# piezo-preamp-tickler_V0-8.net
KiCad netlist of a schematic drawn in EAGLE
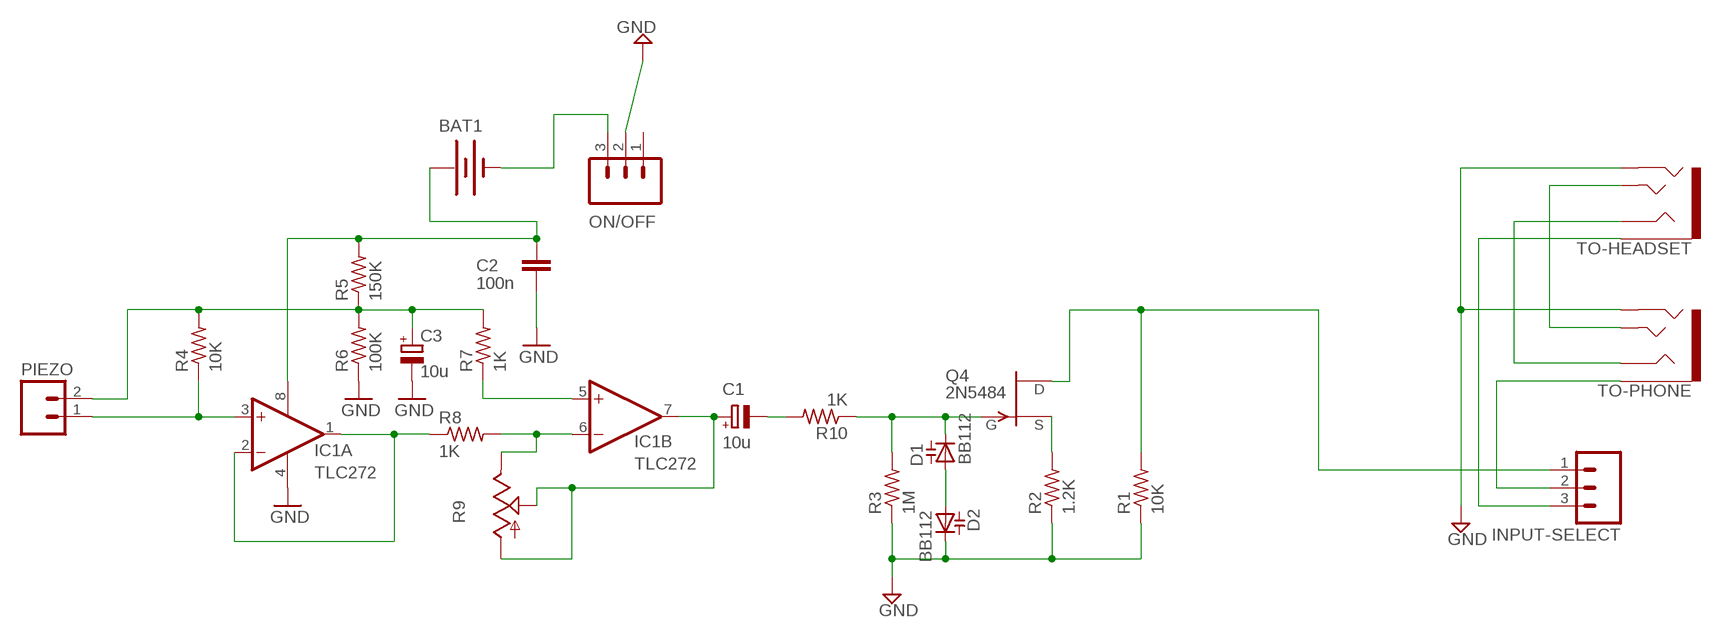
[diagram p0: schematic, sheet 1]

(export (version "E")
  (design (tool "Eeschema 10.0.6"))
  (components
    (comp (ref "BAT1")
      (value "BATTERYA23")
      (footprint "eagle-import:BATTERY-A23")
      (libsource (lib "eagle-import") (part "BATTERYA23"))
    )
    (comp (ref "C1")
      (value "10u")
      (footprint "eagle-import:E2,5-5")
      (libsource (lib "eagle-import") (part "CPOL-EUE2.5-5"))
    )
    (comp (ref "C2")
      (value "100n")
      (footprint "eagle-import:C025-025X050")
      (libsource (lib "eagle-import") (part "C-EU025-025X050"))
    )
    (comp (ref "C3")
      (value "10u")
      (footprint "eagle-import:E2,5-5")
      (libsource (lib "eagle-import") (part "CPOL-EUE2.5-5"))
    )
    (comp (ref "D1")
      (value "BB112")
      (footprint "eagle-import:SOT54H")
      (libsource (lib "eagle-import") (part "BB112"))
    )
    (comp (ref "D2")
      (value "BB112")
      (footprint "eagle-import:SOT54H")
      (libsource (lib "eagle-import") (part "BB112"))
    )
    (comp (ref "IC1")
      (value "TLC272")
      (footprint "eagle-import:DIL08")
      (libsource (lib "eagle-import") (part "TLC272P"))
    )
    (comp (ref "INPUT-SELECT")
      (value "M03SINGLE-POLE-DOUBLE-THROW")
      (footprint "eagle-import:SPDT-SWITCH")
      (libsource (lib "eagle-import") (part "M03SINGLE-POLE-DOUBLE-THROW"))
    )
    (comp (ref "ON/OFF")
      (value "labl")
      (footprint "eagle-import:SPDT-SWITCH")
      (libsource (lib "eagle-import") (part "M03SINGLE-POLE-DOUBLE-THROW"))
    )
    (comp (ref "PIEZO")
      (value "M02LOCK")
      (footprint "eagle-import:1X02_LOCK")
      (libsource (lib "eagle-import") (part "M02LOCK"))
    )
    (comp (ref "Q4")
      (value "2N5484")
      (footprint "eagle-import:TO92-")
      (libsource (lib "eagle-import") (part "?5482N4"))
    )
    (comp (ref "R1")
      (value "10K")
      (footprint "eagle-import:0204V")
      (libsource (lib "eagle-import") (part "R-US_0204/2V"))
    )
    (comp (ref "R2")
      (value "1.2K")
      (footprint "eagle-import:0204V")
      (libsource (lib "eagle-import") (part "R-US_0204/2V"))
    )
    (comp (ref "R3")
      (value "1M")
      (footprint "eagle-import:0204V")
      (libsource (lib "eagle-import") (part "R-US_0204/2V"))
    )
    (comp (ref "R4")
      (value "10K")
      (footprint "eagle-import:0204V")
      (libsource (lib "eagle-import") (part "R-US_0204/2V"))
    )
    (comp (ref "R5")
      (value "150K")
      (footprint "eagle-import:0204V")
      (libsource (lib "eagle-import") (part "R-US_0204/2V"))
    )
    (comp (ref "R6")
      (value "100K")
      (footprint "eagle-import:0204V")
      (libsource (lib "eagle-import") (part "R-US_0204/2V"))
    )
    (comp (ref "R7")
      (value "1K")
      (footprint "eagle-import:0204V")
      (libsource (lib "eagle-import") (part "R-US_0204/2V"))
    )
    (comp (ref "R8")
      (value "1K")
      (footprint "eagle-import:0204V")
      (libsource (lib "eagle-import") (part "R-US_0204/2V"))
    )
    (comp (ref "R9")
      (value "TRIM3386")
      (footprint "eagle-import:TRIM-3386")
      (libsource (lib "eagle-import") (part "TRIM3386"))
    )
    (comp (ref "R10")
      (value "1K")
      (footprint "eagle-import:0204V")
      (libsource (lib "eagle-import") (part "R-US_0204/2V"))
    )
    (comp (ref "TO-HEADSET")
      (value "AUDIO-JACK3LGPADS")
      (footprint "eagle-import:AUDIO-JACK-TRRS-SMD")
      (libsource (lib "eagle-import") (part "AUDIO-JACK3LGPADS"))
    )
    (comp (ref "TO-PHONE")
      (value "AUDIO-JACK3LGPADS")
      (footprint "eagle-import:AUDIO-JACK-TRRS-SMD")
      (libsource (lib "eagle-import") (part "AUDIO-JACK3LGPADS"))
    )
  )
  (nets
    (net (code "1") (name "GND") (class "Default")
      (node (ref "C2") (pin "1") (pinfunction "1_1") (pintype "passive"))
      (node (ref "C3") (pin "-") (pinfunction "-_-") (pintype "passive"))
      (node (ref "D2") (pin "C") (pinfunction "C_C") (pintype "passive"))
      (node (ref "IC1") (pin "4") (pinfunction "V-_4") (pintype "power_in"))
      (node (ref "ON/OFF") (pin "2") (pinfunction "2_2") (pintype "passive"))
      (node (ref "R1") (pin "1") (pinfunction "1_1") (pintype "passive"))
      (node (ref "R2") (pin "1") (pinfunction "1_1") (pintype "passive"))
      (node (ref "R3") (pin "1") (pinfunction "1_1") (pintype "passive"))
      (node (ref "R6") (pin "1") (pinfunction "1_1") (pintype "passive"))
      (node (ref "TO-HEADSET") (pin "RING2") (pinfunction "RING2_RING2") (pintype "bidirectional"))
      (node (ref "TO-PHONE") (pin "RING2") (pinfunction "RING2_RING2") (pintype "bidirectional"))
    )
    (net (code "2") (name "Net-(BAT1-+)") (class "Default")
      (node (ref "BAT1") (pin "PWR@1") (pinfunction "+_PWR@1") (pintype "power_in"))
      (node (ref "C2") (pin "2") (pinfunction "2_2") (pintype "passive"))
      (node (ref "IC1") (pin "8") (pinfunction "V+_8") (pintype "power_in"))
      (node (ref "R5") (pin "2") (pinfunction "2_2") (pintype "passive"))
    )
    (net (code "3") (name "Net-(BAT1--)") (class "Default")
      (node (ref "BAT1") (pin "GND@1") (pinfunction "-_GND@1") (pintype "power_in"))
      (node (ref "ON/OFF") (pin "3") (pinfunction "3_3") (pintype "passive"))
    )
    (net (code "4") (name "Net-(C1-Pad-)") (class "Default")
      (node (ref "C1") (pin "-") (pinfunction "-_-") (pintype "passive"))
      (node (ref "R10") (pin "2") (pinfunction "2_2") (pintype "passive"))
    )
    (net (code "5") (name "Net-(C3-Pad+)") (class "Default")
      (node (ref "C3") (pin "+") (pinfunction "+_+") (pintype "passive"))
      (node (ref "PIEZO") (pin "2") (pinfunction "2_2") (pintype "passive"))
      (node (ref "R4") (pin "2") (pinfunction "2_2") (pintype "passive"))
      (node (ref "R5") (pin "1") (pinfunction "1_1") (pintype "passive"))
      (node (ref "R6") (pin "2") (pinfunction "2_2") (pintype "passive"))
      (node (ref "R7") (pin "2") (pinfunction "2_2") (pintype "passive"))
    )
    (net (code "6") (name "Net-(D1-PadA)") (class "Default")
      (node (ref "D1") (pin "A") (pinfunction "A_A") (pintype "passive"))
      (node (ref "D2") (pin "A") (pinfunction "A_A") (pintype "passive"))
    )
    (net (code "7") (name "Net-(IC1A-+IN)") (class "Default")
      (node (ref "IC1") (pin "3") (pinfunction "+IN_3") (pintype "input"))
      (node (ref "PIEZO") (pin "1") (pinfunction "1_1") (pintype "passive"))
      (node (ref "R4") (pin "1") (pinfunction "1_1") (pintype "passive"))
    )
    (net (code "8") (name "Net-(IC1A--IN)") (class "Default")
      (node (ref "IC1") (pin "1") (pinfunction "OUT_1") (pintype "output"))
      (node (ref "IC1") (pin "2") (pinfunction "-IN_2") (pintype "input"))
      (node (ref "R8") (pin "1") (pinfunction "1_1") (pintype "passive"))
    )
    (net (code "9") (name "Net-(IC1B-+IN)") (class "Default")
      (node (ref "IC1") (pin "5") (pinfunction "+IN_5") (pintype "input"))
      (node (ref "R7") (pin "1") (pinfunction "1_1") (pintype "passive"))
    )
    (net (code "10") (name "Net-(IC1B--IN)") (class "Default")
      (node (ref "IC1") (pin "6") (pinfunction "-IN_6") (pintype "input"))
      (node (ref "R8") (pin "2") (pinfunction "2_2") (pintype "passive"))
      (node (ref "R9") (pin "3") (pinfunction "E_3") (pintype "passive"))
      (node (ref "R9") (pin "6") (pinfunction "E_6") (pintype "passive"))
    )
    (net (code "11") (name "Net-(IC1B-OUT)") (class "Default")
      (node (ref "C1") (pin "+") (pinfunction "+_+") (pintype "passive"))
      (node (ref "IC1") (pin "7") (pinfunction "OUT_7") (pintype "output"))
      (node (ref "R9") (pin "1") (pinfunction "A_1") (pintype "passive"))
      (node (ref "R9") (pin "2") (pinfunction "S_2") (pintype "passive"))
      (node (ref "R9") (pin "4") (pinfunction "A_4") (pintype "passive"))
      (node (ref "R9") (pin "5") (pinfunction "S_5") (pintype "passive"))
    )
    (net (code "12") (name "Net-(INPUT-SELECT-Pad2)") (class "Default")
      (node (ref "INPUT-SELECT") (pin "2") (pinfunction "2_2") (pintype "passive"))
      (node (ref "TO-PHONE") (pin "EARTH") (pinfunction "EARTH_EARTH") (pintype "bidirectional"))
    )
    (net (code "13") (name "Net-(INPUT-SELECT-Pad3)") (class "Default")
      (node (ref "INPUT-SELECT") (pin "3") (pinfunction "3_3") (pintype "passive"))
      (node (ref "TO-HEADSET") (pin "EARTH") (pinfunction "EARTH_EARTH") (pintype "bidirectional"))
    )
    (net (code "14") (name "Net-(Q4-D)") (class "Default")
      (node (ref "INPUT-SELECT") (pin "1") (pinfunction "1_1") (pintype "passive"))
      (node (ref "Q4") (pin "3") (pinfunction "D_3") (pintype "passive"))
      (node (ref "R1") (pin "2") (pinfunction "2_2") (pintype "passive"))
    )
    (net (code "15") (name "Net-(Q4-G)") (class "Default")
      (node (ref "D1") (pin "C") (pinfunction "C_C") (pintype "passive"))
      (node (ref "Q4") (pin "1") (pinfunction "G_1") (pintype "passive"))
      (node (ref "R10") (pin "1") (pinfunction "1_1") (pintype "passive"))
      (node (ref "R3") (pin "2") (pinfunction "2_2") (pintype "passive"))
    )
    (net (code "16") (name "Net-(Q4-S)") (class "Default")
      (node (ref "Q4") (pin "2") (pinfunction "S_2") (pintype "passive"))
      (node (ref "R2") (pin "2") (pinfunction "2_2") (pintype "passive"))
    )
    (net (code "17") (name "Net-(TO-HEADSET-PadRING1)") (class "Default")
      (node (ref "TO-HEADSET") (pin "RING1") (pinfunction "RING1_RING1") (pintype "bidirectional"))
      (node (ref "TO-PHONE") (pin "RING1") (pinfunction "RING1_RING1") (pintype "bidirectional"))
    )
    (net (code "18") (name "Net-(TO-HEADSET-PadTIP)") (class "Default")
      (node (ref "TO-HEADSET") (pin "TIP") (pinfunction "TIP_TIP") (pintype "bidirectional"))
      (node (ref "TO-PHONE") (pin "TIP") (pinfunction "TIP_TIP") (pintype "bidirectional"))
    )
    (net (code "19") (name "unconnected-(ON/OFF-Pad1)") (class "Default")
      (node (ref "ON/OFF") (pin "1") (pinfunction "1_1") (pintype "passive"))
    )
  )
)
